# SmartSwitch.net
KiCad netlist of a schematic drawn in EAGLE
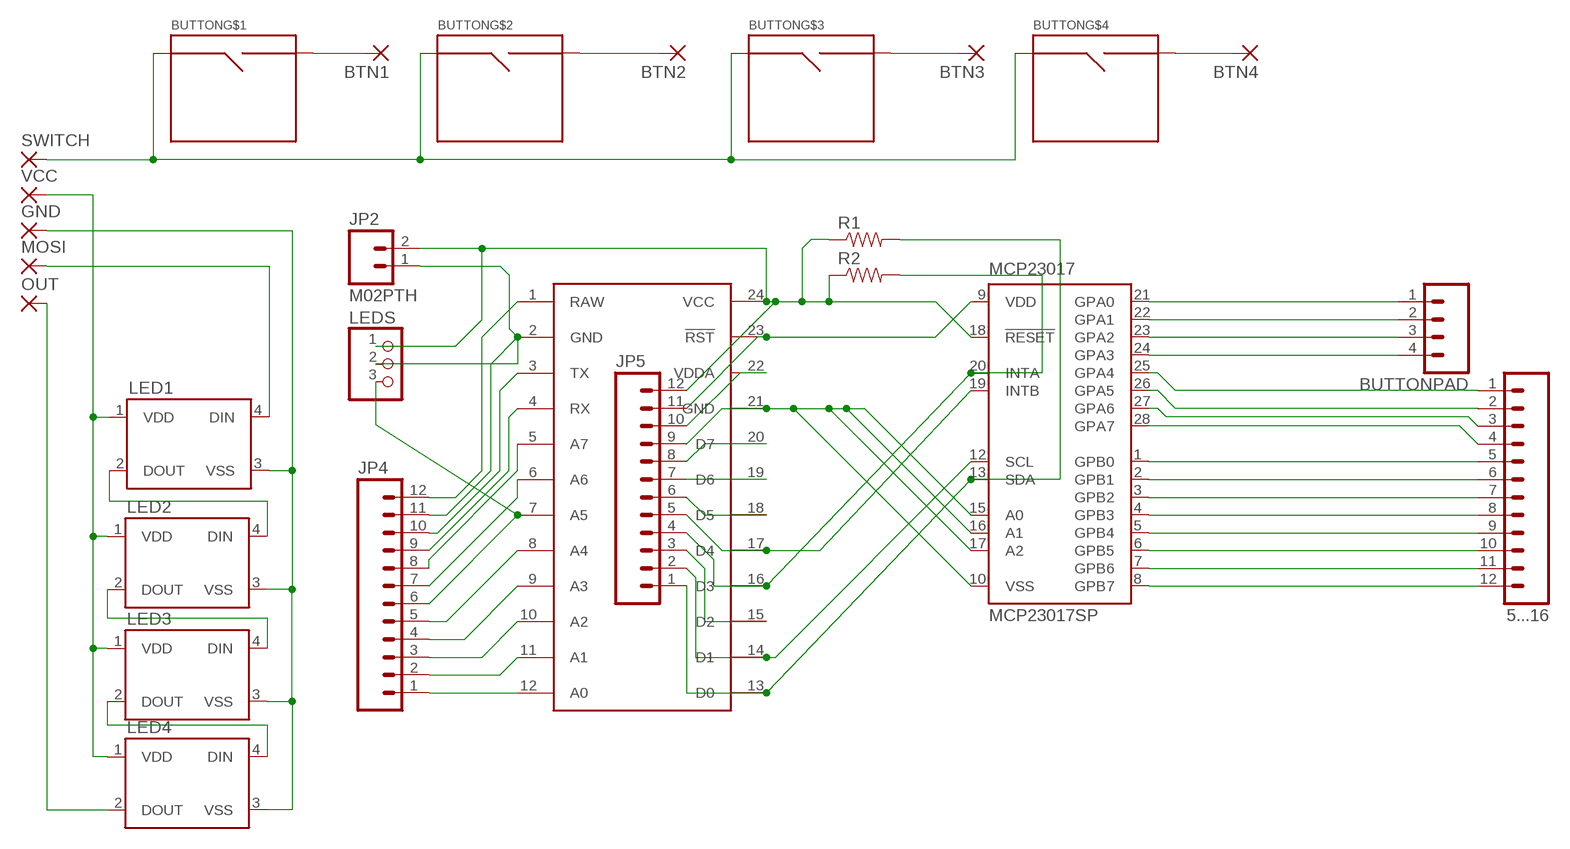
[diagram p0: schematic, sheet 1]

(export (version "E")
  (design (tool "Eeschema 10.0.6"))
  (components
    (comp (ref "5...16")
      (value "M12PTH")
      (footprint "eagle-import:1X12")
      (libsource (lib "eagle-import") (part "SparkFun-Connectors_M12PTH"))
    )
    (comp (ref "BTN1")
      (value "2,15/1,0")
      (footprint "eagle-import:2,15_1,0")
      (libsource (lib "eagle-import") (part "2,15/1,0"))
    )
    (comp (ref "BTN2")
      (value "2,15/1,0")
      (footprint "eagle-import:2,15_1,0")
      (libsource (lib "eagle-import") (part "2,15/1,0"))
    )
    (comp (ref "BTN3")
      (value "2,15/1,0")
      (footprint "eagle-import:2,15_1,0")
      (libsource (lib "eagle-import") (part "2,15/1,0"))
    )
    (comp (ref "BTN4")
      (value "2,15/1,0")
      (footprint "eagle-import:2,15_1,0")
      (libsource (lib "eagle-import") (part "2,15/1,0"))
    )
    (comp (ref "BUTTON")
      (value "BUTTON")
      (footprint "eagle-import:BUTTON")
      (libsource (lib "eagle-import") (part "BUTTON"))
    )
    (comp (ref "BUTTONPAD")
      (value "M04PTH")
      (footprint "eagle-import:1X04")
      (libsource (lib "eagle-import") (part "M04PTH"))
    )
    (comp (ref "GND")
      (value "2,15/1,0")
      (footprint "eagle-import:2,15_1,0")
      (libsource (lib "eagle-import") (part "2,15/1,0"))
    )
    (comp (ref "JP2")
      (value "M02PTH")
      (footprint "eagle-import:1X02")
      (libsource (lib "eagle-import") (part "M02PTH"))
    )
    (comp (ref "JP4")
      (value "M12PTH")
      (footprint "eagle-import:1X12-SMALL-PADS")
      (libsource (lib "eagle-import") (part "M12PTH"))
    )
    (comp (ref "JP5")
      (value "M12PTH")
      (footprint "eagle-import:1X12-SMALL-PADS")
      (libsource (lib "eagle-import") (part "M12PTH"))
    )
    (comp (ref "LED1")
      (value "WS2812B")
      (footprint "eagle-import:WS2812B")
      (libsource (lib "eagle-import") (part "WS2812B"))
    )
    (comp (ref "LED2")
      (value "WS2812B")
      (footprint "eagle-import:WS2812B")
      (libsource (lib "eagle-import") (part "WS2812B"))
    )
    (comp (ref "LED3")
      (value "WS2812B")
      (footprint "eagle-import:WS2812B")
      (libsource (lib "eagle-import") (part "WS2812B"))
    )
    (comp (ref "LED4")
      (value "WS2812B")
      (footprint "eagle-import:WS2812B")
      (libsource (lib "eagle-import") (part "WS2812B"))
    )
    (comp (ref "LEDS")
      (value "PINHD-1X3")
      (footprint "eagle-import:1X03")
      (libsource (lib "eagle-import") (part "PINHD-1X3"))
    )
    (comp (ref "MCP23017")
      (value "MCP23017SP")
      (footprint "eagle-import:DIL28-3")
      (libsource (lib "eagle-import") (part "MCP23017SP"))
    )
    (comp (ref "MOSI")
      (value "2,15/1,0")
      (footprint "eagle-import:2,15_1,0")
      (libsource (lib "eagle-import") (part "2,15/1,0"))
    )
    (comp (ref "OUT")
      (value "2,15/1,0")
      (footprint "eagle-import:2,15_1,0")
      (libsource (lib "eagle-import") (part "2,15/1,0"))
    )
    (comp (ref "R1")
      (value "RESISTORPTH-1/2W")
      (footprint "eagle-import:AXIAL-0.5")
      (libsource (lib "eagle-import") (part "RESISTORPTH-1/2W"))
    )
    (comp (ref "R2")
      (value "RESISTORPTH-1/2W")
      (footprint "eagle-import:AXIAL-0.5")
      (libsource (lib "eagle-import") (part "RESISTORPTH-1/2W"))
    )
    (comp (ref "SPARK")
      (value "SPARK_CORECORE")
      (footprint "eagle-import:SPARK_CORE")
      (libsource (lib "eagle-import") (part "SPARK_CORECORE"))
    )
    (comp (ref "SWITCH")
      (value "2,15/1,0")
      (footprint "eagle-import:2,15_1,0")
      (libsource (lib "eagle-import") (part "2,15/1,0"))
    )
    (comp (ref "VCC")
      (value "2,15/1,0")
      (footprint "eagle-import:2,15_1,0")
      (libsource (lib "eagle-import") (part "2,15/1,0"))
    )
  )
  (nets
    (net (code "1") (name "Net-(BTN1-P)") (class "Default")
      (node (ref "BTN1") (pin "1") (pinfunction "P_1") (pintype "passive"))
      (node (ref "BUTTON") (pin "SIG2") (pinfunction "SIG2_SIG2") (pintype "bidirectional"))
    )
    (net (code "2") (name "Net-(BTN2-P)") (class "Default")
      (node (ref "BTN2") (pin "1") (pinfunction "P_1") (pintype "passive"))
      (node (ref "BUTTON") (pin "SIG4") (pinfunction "SIG2_SIG4") (pintype "bidirectional"))
    )
    (net (code "3") (name "Net-(BTN3-P)") (class "Default")
      (node (ref "BTN3") (pin "1") (pinfunction "P_1") (pintype "passive"))
      (node (ref "BUTTON") (pin "SIG6") (pinfunction "SIG2_SIG6") (pintype "bidirectional"))
    )
    (net (code "4") (name "Net-(BTN4-P)") (class "Default")
      (node (ref "BTN4") (pin "1") (pinfunction "P_1") (pintype "passive"))
      (node (ref "BUTTON") (pin "SIG8") (pinfunction "SIG2_SIG8") (pintype "bidirectional"))
    )
    (net (code "5") (name "Net-(BUTTONB-SIG1)") (class "Default")
      (node (ref "BUTTON") (pin "SIG1") (pinfunction "SIG1_SIG1") (pintype "bidirectional"))
      (node (ref "BUTTON") (pin "SIG3") (pinfunction "SIG1_SIG3") (pintype "bidirectional"))
      (node (ref "BUTTON") (pin "SIG5") (pinfunction "SIG1_SIG5") (pintype "bidirectional"))
      (node (ref "BUTTON") (pin "SIG7") (pinfunction "SIG1_SIG7") (pintype "bidirectional"))
      (node (ref "SWITCH") (pin "1") (pinfunction "P_1") (pintype "passive"))
    )
    (net (code "6") (name "Net-(GND-P)") (class "Default")
      (node (ref "GND") (pin "1") (pinfunction "P_1") (pintype "passive"))
      (node (ref "LED1") (pin "3") (pinfunction "VSS_3") (pintype "power_in"))
      (node (ref "LED2") (pin "3") (pinfunction "VSS_3") (pintype "power_in"))
      (node (ref "LED3") (pin "3") (pinfunction "VSS_3") (pintype "power_in"))
      (node (ref "LED4") (pin "3") (pinfunction "VSS_3") (pintype "power_in"))
    )
    (net (code "7") (name "Net-(JP2-Pad1)") (class "Default")
      (node (ref "JP2") (pin "1") (pinfunction "1_1") (pintype "passive"))
      (node (ref "JP4") (pin "11") (pinfunction "11_11") (pintype "passive"))
      (node (ref "LEDS") (pin "2") (pinfunction "2_2") (pintype "passive"))
      (node (ref "SPARK") (pin "2") (pinfunction "GND_2") (pintype "power_in"))
    )
    (net (code "8") (name "Net-(LED1-DIN)") (class "Default")
      (node (ref "LED1") (pin "4") (pinfunction "DIN_4") (pintype "input"))
      (node (ref "MOSI") (pin "1") (pinfunction "P_1") (pintype "passive"))
    )
    (net (code "9") (name "Net-(LED1-DOUT)") (class "Default")
      (node (ref "LED1") (pin "2") (pinfunction "DOUT_2") (pintype "output"))
      (node (ref "LED2") (pin "4") (pinfunction "DIN_4") (pintype "input"))
    )
    (net (code "10") (name "Net-(LED1-VDD)") (class "Default")
      (node (ref "LED1") (pin "1") (pinfunction "VDD_1") (pintype "power_in"))
      (node (ref "LED2") (pin "1") (pinfunction "VDD_1") (pintype "power_in"))
      (node (ref "LED3") (pin "1") (pinfunction "VDD_1") (pintype "power_in"))
      (node (ref "LED4") (pin "1") (pinfunction "VDD_1") (pintype "power_in"))
      (node (ref "VCC") (pin "1") (pinfunction "P_1") (pintype "passive"))
    )
    (net (code "11") (name "Net-(LED2-DOUT)") (class "Default")
      (node (ref "LED2") (pin "2") (pinfunction "DOUT_2") (pintype "output"))
      (node (ref "LED3") (pin "4") (pinfunction "DIN_4") (pintype "input"))
    )
    (net (code "12") (name "Net-(LED3-DOUT)") (class "Default")
      (node (ref "LED3") (pin "2") (pinfunction "DOUT_2") (pintype "output"))
      (node (ref "LED4") (pin "4") (pinfunction "DIN_4") (pintype "input"))
    )
    (net (code "13") (name "Net-(LED4-DOUT)") (class "Default")
      (node (ref "LED4") (pin "2") (pinfunction "DOUT_2") (pintype "output"))
      (node (ref "OUT") (pin "1") (pinfunction "P_1") (pintype "passive"))
    )
    (net (code "14") (name "Net-(MCP23017-A0)") (class "Default")
      (node (ref "JP5") (pin "9") (pinfunction "9_9") (pintype "passive"))
      (node (ref "MCP23017") (pin "10") (pinfunction "VSS_10") (pintype "power_in"))
      (node (ref "MCP23017") (pin "15") (pinfunction "A0_15") (pintype "input"))
      (node (ref "MCP23017") (pin "16") (pinfunction "A1_16") (pintype "input"))
      (node (ref "MCP23017") (pin "17") (pinfunction "A2_17") (pintype "input"))
      (node (ref "SPARK") (pin "21") (pinfunction "GND_21") (pintype "power_in"))
    )
    (net (code "15") (name "Net-(MCP23017-GPA0)") (class "Default")
      (node (ref "BUTTONPAD") (pin "1") (pinfunction "1_1") (pintype "passive"))
      (node (ref "MCP23017") (pin "21") (pinfunction "GPA0_21") (pintype "bidirectional"))
    )
    (net (code "16") (name "Net-(MCP23017-GPA1)") (class "Default")
      (node (ref "BUTTONPAD") (pin "2") (pinfunction "2_2") (pintype "passive"))
      (node (ref "MCP23017") (pin "22") (pinfunction "GPA1_22") (pintype "bidirectional"))
    )
    (net (code "17") (name "Net-(MCP23017-GPA2)") (class "Default")
      (node (ref "BUTTONPAD") (pin "3") (pinfunction "3_3") (pintype "passive"))
      (node (ref "MCP23017") (pin "23") (pinfunction "GPA2_23") (pintype "bidirectional"))
    )
    (net (code "18") (name "Net-(MCP23017-GPA3)") (class "Default")
      (node (ref "BUTTONPAD") (pin "4") (pinfunction "4_4") (pintype "passive"))
      (node (ref "MCP23017") (pin "24") (pinfunction "GPA3_24") (pintype "bidirectional"))
    )
    (net (code "19") (name "Net-(MCP23017-GPA4)") (class "Default")
      (node (ref "5...16") (pin "1") (pinfunction "1_1") (pintype "passive"))
      (node (ref "MCP23017") (pin "25") (pinfunction "GPA4_25") (pintype "bidirectional"))
    )
    (net (code "20") (name "Net-(MCP23017-GPA5)") (class "Default")
      (node (ref "5...16") (pin "2") (pinfunction "2_2") (pintype "passive"))
      (node (ref "MCP23017") (pin "26") (pinfunction "GPA5_26") (pintype "bidirectional"))
    )
    (net (code "21") (name "Net-(MCP23017-GPA6)") (class "Default")
      (node (ref "5...16") (pin "3") (pinfunction "3_3") (pintype "passive"))
      (node (ref "MCP23017") (pin "27") (pinfunction "GPA6_27") (pintype "bidirectional"))
    )
    (net (code "22") (name "Net-(MCP23017-GPA7)") (class "Default")
      (node (ref "5...16") (pin "4") (pinfunction "4_4") (pintype "passive"))
      (node (ref "MCP23017") (pin "28") (pinfunction "GPA7_28") (pintype "bidirectional"))
    )
    (net (code "23") (name "Net-(MCP23017-GPB0)") (class "Default")
      (node (ref "5...16") (pin "5") (pinfunction "5_5") (pintype "passive"))
      (node (ref "MCP23017") (pin "1") (pinfunction "GPB0_1") (pintype "bidirectional"))
    )
    (net (code "24") (name "Net-(MCP23017-GPB1)") (class "Default")
      (node (ref "5...16") (pin "6") (pinfunction "6_6") (pintype "passive"))
      (node (ref "MCP23017") (pin "2") (pinfunction "GPB1_2") (pintype "bidirectional"))
    )
    (net (code "25") (name "Net-(MCP23017-GPB2)") (class "Default")
      (node (ref "5...16") (pin "7") (pinfunction "7_7") (pintype "passive"))
      (node (ref "MCP23017") (pin "3") (pinfunction "GPB2_3") (pintype "bidirectional"))
    )
    (net (code "26") (name "Net-(MCP23017-GPB3)") (class "Default")
      (node (ref "5...16") (pin "8") (pinfunction "8_8") (pintype "passive"))
      (node (ref "MCP23017") (pin "4") (pinfunction "GPB3_4") (pintype "bidirectional"))
    )
    (net (code "27") (name "Net-(MCP23017-GPB4)") (class "Default")
      (node (ref "5...16") (pin "9") (pinfunction "9_9") (pintype "passive"))
      (node (ref "MCP23017") (pin "5") (pinfunction "GPB4_5") (pintype "bidirectional"))
    )
    (net (code "28") (name "Net-(MCP23017-GPB5)") (class "Default")
      (node (ref "5...16") (pin "10") (pinfunction "10_10") (pintype "passive"))
      (node (ref "MCP23017") (pin "6") (pinfunction "GPB5_6") (pintype "bidirectional"))
    )
    (net (code "29") (name "Net-(MCP23017-GPB6)") (class "Default")
      (node (ref "5...16") (pin "11") (pinfunction "11_11") (pintype "passive"))
      (node (ref "MCP23017") (pin "7") (pinfunction "GPB6_7") (pintype "bidirectional"))
    )
    (net (code "30") (name "Net-(MCP23017-GPB7)") (class "Default")
      (node (ref "5...16") (pin "12") (pinfunction "12_12") (pintype "passive"))
      (node (ref "MCP23017") (pin "8") (pinfunction "GPB7_8") (pintype "bidirectional"))
    )
    (net (code "31") (name "Net-(MCP23017-INTA)") (class "Default")
      (node (ref "JP5") (pin "4") (pinfunction "4_4") (pintype "passive"))
      (node (ref "MCP23017") (pin "20") (pinfunction "INTA_20") (pintype "output"))
      (node (ref "R2") (pin "P$2") (pinfunction "2_P$2") (pintype "passive"))
      (node (ref "SPARK") (pin "16") (pinfunction "D3_16") (pintype "bidirectional"))
    )
    (net (code "32") (name "Net-(MCP23017-INTB)") (class "Default")
      (node (ref "JP5") (pin "5") (pinfunction "5_5") (pintype "passive"))
      (node (ref "MCP23017") (pin "19") (pinfunction "INTB_19") (pintype "output"))
      (node (ref "SPARK") (pin "17") (pinfunction "D4_17") (pintype "bidirectional"))
    )
    (net (code "33") (name "Net-(MCP23017-SCL)") (class "Default")
      (node (ref "JP5") (pin "2") (pinfunction "2_2") (pintype "passive"))
      (node (ref "MCP23017") (pin "12") (pinfunction "SCL_12") (pintype "input"))
      (node (ref "SPARK") (pin "14") (pinfunction "D1_14") (pintype "bidirectional"))
    )
    (net (code "34") (name "Net-(MCP23017-SDA)") (class "Default")
      (node (ref "JP5") (pin "1") (pinfunction "1_1") (pintype "passive"))
      (node (ref "MCP23017") (pin "13") (pinfunction "SDA_13") (pintype "bidirectional"))
      (node (ref "R1") (pin "P$2") (pinfunction "2_P$2") (pintype "passive"))
      (node (ref "SPARK") (pin "13") (pinfunction "D0_13") (pintype "bidirectional"))
    )
    (net (code "35") (name "Net-(MCP23017-VDD)") (class "Default")
      (node (ref "JP5") (pin "11") (pinfunction "11_11") (pintype "passive"))
      (node (ref "MCP23017") (pin "9") (pinfunction "VDD_9") (pintype "power_in"))
      (node (ref "SPARK") (pin "23") (pinfunction "~{RST}_23") (pintype "bidirectional"))
    )
    (net (code "36") (name "Net-(MCP23017-~{RESET})") (class "Default")
      (node (ref "JP2") (pin "2") (pinfunction "2_2") (pintype "passive"))
      (node (ref "JP5") (pin "12") (pinfunction "12_12") (pintype "passive"))
      (node (ref "LEDS") (pin "1") (pinfunction "1_1") (pintype "passive"))
      (node (ref "MCP23017") (pin "18") (pinfunction "~{RESET}_18") (pintype "input"))
      (node (ref "R1") (pin "P$1") (pinfunction "1_P$1") (pintype "passive"))
      (node (ref "R2") (pin "P$1") (pinfunction "1_P$1") (pintype "passive"))
      (node (ref "SPARK") (pin "24") (pinfunction "VCC_24") (pintype "power_in"))
    )
    (net (code "37") (name "Net-(SPARK-A0)") (class "Default")
      (node (ref "JP4") (pin "1") (pinfunction "1_1") (pintype "passive"))
      (node (ref "SPARK") (pin "12") (pinfunction "A0_12") (pintype "bidirectional"))
    )
    (net (code "38") (name "Net-(SPARK-A1)") (class "Default")
      (node (ref "JP4") (pin "2") (pinfunction "2_2") (pintype "passive"))
      (node (ref "SPARK") (pin "11") (pinfunction "A1_11") (pintype "bidirectional"))
    )
    (net (code "39") (name "Net-(SPARK-A2)") (class "Default")
      (node (ref "JP4") (pin "3") (pinfunction "3_3") (pintype "passive"))
      (node (ref "SPARK") (pin "10") (pinfunction "A2_10") (pintype "bidirectional"))
    )
    (net (code "40") (name "Net-(SPARK-A3)") (class "Default")
      (node (ref "JP4") (pin "4") (pinfunction "4_4") (pintype "passive"))
      (node (ref "SPARK") (pin "9") (pinfunction "A3_9") (pintype "bidirectional"))
    )
    (net (code "41") (name "Net-(SPARK-A4)") (class "Default")
      (node (ref "JP4") (pin "5") (pinfunction "5_5") (pintype "passive"))
      (node (ref "SPARK") (pin "8") (pinfunction "A4_8") (pintype "bidirectional"))
    )
    (net (code "42") (name "Net-(SPARK-A5)") (class "Default")
      (node (ref "JP4") (pin "6") (pinfunction "6_6") (pintype "passive"))
      (node (ref "LEDS") (pin "3") (pinfunction "3_3") (pintype "passive"))
      (node (ref "SPARK") (pin "7") (pinfunction "A5_7") (pintype "bidirectional"))
    )
    (net (code "43") (name "Net-(SPARK-A6)") (class "Default")
      (node (ref "JP4") (pin "7") (pinfunction "7_7") (pintype "passive"))
      (node (ref "SPARK") (pin "6") (pinfunction "A6_6") (pintype "bidirectional"))
    )
    (net (code "44") (name "Net-(SPARK-A7)") (class "Default")
      (node (ref "JP4") (pin "8") (pinfunction "8_8") (pintype "passive"))
      (node (ref "SPARK") (pin "5") (pinfunction "A7_5") (pintype "bidirectional"))
    )
    (net (code "45") (name "Net-(SPARK-D2)") (class "Default")
      (node (ref "JP5") (pin "3") (pinfunction "3_3") (pintype "passive"))
      (node (ref "SPARK") (pin "15") (pinfunction "D2_15") (pintype "bidirectional"))
    )
    (net (code "46") (name "Net-(SPARK-D5)") (class "Default")
      (node (ref "JP5") (pin "6") (pinfunction "6_6") (pintype "passive"))
      (node (ref "SPARK") (pin "18") (pinfunction "D5_18") (pintype "bidirectional"))
    )
    (net (code "47") (name "Net-(SPARK-D6)") (class "Default")
      (node (ref "JP5") (pin "7") (pinfunction "7_7") (pintype "passive"))
      (node (ref "SPARK") (pin "19") (pinfunction "D6_19") (pintype "bidirectional"))
    )
    (net (code "48") (name "Net-(SPARK-D7)") (class "Default")
      (node (ref "JP5") (pin "8") (pinfunction "8_8") (pintype "passive"))
      (node (ref "SPARK") (pin "20") (pinfunction "D7_20") (pintype "bidirectional"))
    )
    (net (code "49") (name "Net-(SPARK-RAW)") (class "Default")
      (node (ref "JP4") (pin "12") (pinfunction "12_12") (pintype "passive"))
      (node (ref "SPARK") (pin "1") (pinfunction "RAW_1") (pintype "power_in"))
    )
    (net (code "50") (name "Net-(SPARK-RX)") (class "Default")
      (node (ref "JP4") (pin "9") (pinfunction "9_9") (pintype "passive"))
      (node (ref "SPARK") (pin "4") (pinfunction "RX_4") (pintype "bidirectional"))
    )
    (net (code "51") (name "Net-(SPARK-TX)") (class "Default")
      (node (ref "JP4") (pin "10") (pinfunction "10_10") (pintype "passive"))
      (node (ref "SPARK") (pin "3") (pinfunction "TX_3") (pintype "bidirectional"))
    )
    (net (code "52") (name "Net-(SPARK-VDDA)") (class "Default")
      (node (ref "JP5") (pin "10") (pinfunction "10_10") (pintype "passive"))
      (node (ref "SPARK") (pin "22") (pinfunction "VDDA_22") (pintype "power_in"))
    )
  )
)
